# USB_Data_isolation.net
KiCad netlist of a schematic drawn in Altium Designer
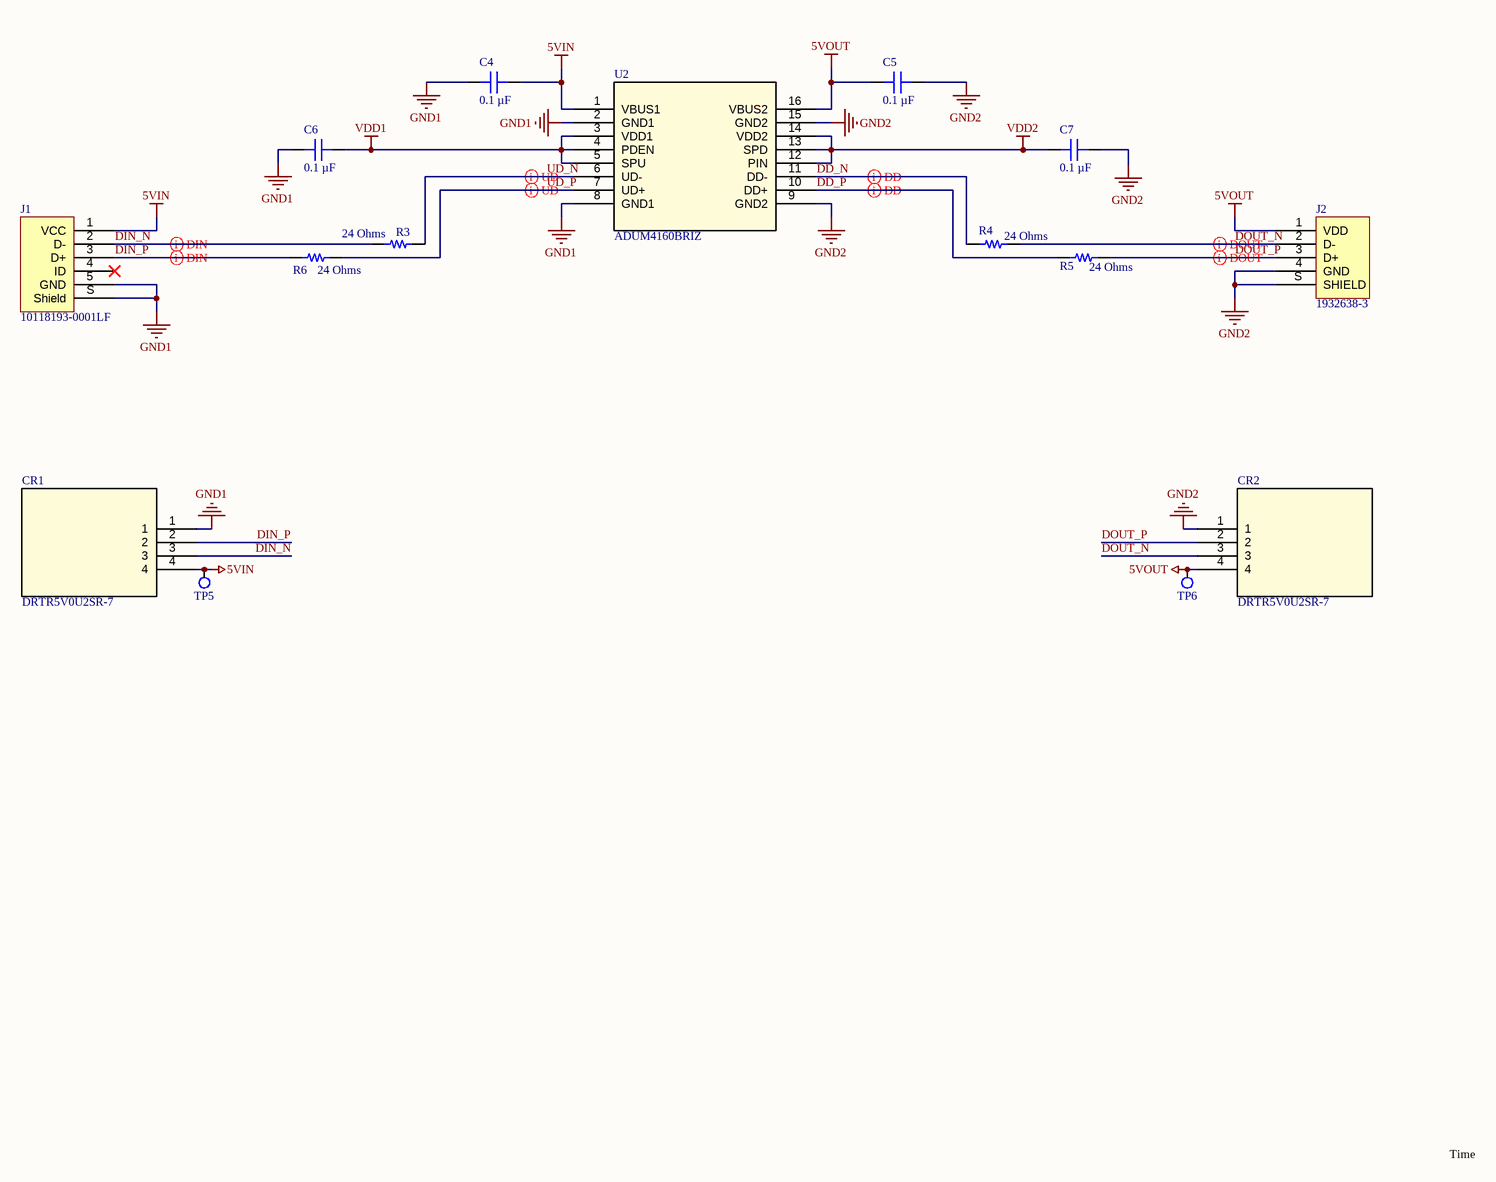
[diagram p0: USB Data isolation.SchDoc]

(export (version "E")
  (design (tool "Eeschema 10.0.6"))
  (components
    (comp (ref "C4")
      (value "0.1 µF")
      (footprint "CAP 0603_1608")
      (description "CAP CER 0.1UF 50V X7R 0603")
      (fields
        (field (name "PART NUMBER") "CL10B104KB8NNNL")
        (field (name "MANUFACTURER") "Samsung Electro-Mechanics")
      )
      (libsource (lib "Celestial Altium Library - altium_library") (part "Capacitor"))
    )
    (comp (ref "C5")
      (value "0.1 µF")
      (footprint "CAP 0603_1608")
      (description "CAP CER 0.1UF 50V X7R 0603")
      (fields
        (field (name "PART NUMBER") "CL10B104KB8NNNL")
        (field (name "MANUFACTURER") "Samsung Electro-Mechanics")
      )
      (libsource (lib "Celestial Altium Library - altium_library") (part "Capacitor"))
    )
    (comp (ref "C6")
      (value "0.1 µF")
      (footprint "CAP 0603_1608")
      (description "CAP CER 0.1UF 50V X7R 0603")
      (fields
        (field (name "PART NUMBER") "CL10B104KB8NNNL")
        (field (name "MANUFACTURER") "Samsung Electro-Mechanics")
      )
      (libsource (lib "Celestial Altium Library - altium_library") (part "Capacitor"))
    )
    (comp (ref "C7")
      (value "0.1 µF")
      (footprint "CAP 0603_1608")
      (description "CAP CER 0.1UF 50V X7R 0603")
      (fields
        (field (name "PART NUMBER") "CL10B104KB8NNNL")
        (field (name "MANUFACTURER") "Samsung Electro-Mechanics")
      )
      (libsource (lib "Celestial Altium Library - altium_library") (part "Capacitor"))
    )
    (comp (ref "CR1")
      (value "DRTR5V0U2SR-7")
      (footprint "SOT143_DIO")
      (description "Dual Channel 5.5 V 0.4 W 1 pF Uni-Dirirectional TVS Diode Array - SOT-143")
      (fields
        (field (name "MANUFACTURER") "Diodes")
        (field (name "COPYRIGHT") "Copyright (C) 2022 Ultra Librarian. All rights reserved.")
      )
      (libsource (lib "") (part "DRTR5V0U2SR-7_1"))
    )
    (comp (ref "CR2")
      (value "DRTR5V0U2SR-7")
      (footprint "SOT143_DIO")
      (description "Dual Channel 5.5 V 0.4 W 1 pF Uni-Dirirectional TVS Diode Array - SOT-143")
      (fields
        (field (name "MANUFACTURER") "Diodes")
        (field (name "COPYRIGHT") "Copyright (C) 2022 Ultra Librarian. All rights reserved.")
      )
      (libsource (lib "USB_isolator") (part "DRTR5V0U2SR-7"))
    )
    (comp (ref "J1")
      (value "10118193-0001LF")
      (footprint "FCI USB 10118193-0001LF")
      (description "CONN RCPT USB2.0 MICRO B SMD R/A")
      (fields (field (name "MANUFACTURER") "Amphenol ICC (FCI)"))
      (libsource (lib "Celestial Altium Library - altium_library") (part "USB 2.0 Type B Micro"))
    )
    (comp (ref "J2")
      (value "1932638-3")
      (footprint "TE 1932638-3 USB2.0A")
      (description "CONN RCPT USB2.0 TYPEA 4P SMD RA")
      (fields (field (name "MANUFACTURER") "TE Connectivity AMP Connectors"))
      (libsource (lib "Celestial Altium Library - altium_library") (part "TE 1932638-3"))
    )
    (comp (ref "R3")
      (value "24 Ohms")
      (footprint "RES 0603_1608")
      (description "RES SMD 24 OHM 0.1% 1/16W 0603")
      (fields
        (field (name "PART NUMBER") "CPF0603B24RE1")
        (field (name "MANUFACTURER") "TE Connectivity Passive Product")
      )
      (libsource (lib "Celestial Altium Library - altium_library") (part "Resistor"))
    )
    (comp (ref "R4")
      (value "24 Ohms")
      (footprint "RES 0603_1608")
      (description "RES SMD 24 OHM 0.1% 1/16W 0603")
      (fields
        (field (name "PART NUMBER") "CPF0603B24RE1")
        (field (name "MANUFACTURER") "TE Connectivity Passive Product")
      )
      (libsource (lib "Celestial Altium Library - altium_library") (part "Resistor"))
    )
    (comp (ref "R5")
      (value "24 Ohms")
      (footprint "RES 0603_1608")
      (description "RES SMD 24 OHM 0.1% 1/16W 0603")
      (fields
        (field (name "PART NUMBER") "CPF0603B24RE1")
        (field (name "MANUFACTURER") "TE Connectivity Passive Product")
      )
      (libsource (lib "Celestial Altium Library - altium_library") (part "Resistor"))
    )
    (comp (ref "R6")
      (value "24 Ohms")
      (footprint "RES 0603_1608")
      (description "RES SMD 24 OHM 0.1% 1/16W 0603")
      (fields
        (field (name "PART NUMBER") "CPF0603B24RE1")
        (field (name "MANUFACTURER") "TE Connectivity Passive Product")
      )
      (libsource (lib "Celestial Altium Library - altium_library") (part "Resistor"))
    )
    (comp (ref "TP5")
      (value "Testpoint_1")
      (footprint "Testpoint_1")
      (description "Testpoint")
      (libsource (lib "USB_isolator") (part "Testpoint_1"))
    )
    (comp (ref "TP6")
      (value "Testpoint_1")
      (footprint "Testpoint_1")
      (description "Testpoint")
      (libsource (lib "USB_isolator") (part "Testpoint_1"))
    )
    (comp (ref "U2")
      (value "ADUM4160BRIZ")
      (footprint "RI_16_1_ADI")
      (description "USB Digital Isolator 5000Vrms 1 Channel 12Mbps 25kV/µs CMTI 16-SOIC (0.295\", 7.50mm Width)")
      (fields (field (name "COPYRIGHT") "Copyright (C) 2022 Ultra Librarian. All rights reserved."))
      (libsource (lib "USB_isolator") (part "ADUM4160BRIZ"))
    )
  )
  (nets
    (net (code "1") (name "/DD_N") (class "Default")
      (node (ref "R4") (pin "1") (pinfunction "1_1") (pintype "passive"))
      (node (ref "U2") (pin "11") (pinfunction "DD-_11") (pintype "passive"))
    )
    (net (code "2") (name "/DD_P") (class "Default")
      (node (ref "R5") (pin "1") (pinfunction "1_1") (pintype "passive"))
      (node (ref "U2") (pin "10") (pinfunction "DD+_10") (pintype "passive"))
    )
    (net (code "3") (name "/DIN_N") (class "Default")
      (node (ref "CR1") (pin "3") (pinfunction "3_3") (pintype "passive"))
      (node (ref "J1") (pin "2") (pinfunction "D-_2") (pintype "passive"))
      (node (ref "R3") (pin "1") (pinfunction "1_1") (pintype "passive"))
    )
    (net (code "4") (name "/DIN_P") (class "Default")
      (node (ref "CR1") (pin "2") (pinfunction "2_2") (pintype "passive"))
      (node (ref "J1") (pin "3") (pinfunction "D+_3") (pintype "passive"))
      (node (ref "R6") (pin "1") (pinfunction "1_1") (pintype "passive"))
    )
    (net (code "5") (name "/DOUT_N") (class "Default")
      (node (ref "CR2") (pin "3") (pinfunction "3_3") (pintype "passive"))
      (node (ref "J2") (pin "2") (pinfunction "D-_2") (pintype "passive"))
      (node (ref "R4") (pin "2") (pinfunction "2_2") (pintype "passive"))
    )
    (net (code "6") (name "/DOUT_P") (class "Default")
      (node (ref "CR2") (pin "2") (pinfunction "2_2") (pintype "passive"))
      (node (ref "J2") (pin "3") (pinfunction "D+_3") (pintype "passive"))
      (node (ref "R5") (pin "2") (pinfunction "2_2") (pintype "passive"))
    )
    (net (code "7") (name "/UD_N") (class "Default")
      (node (ref "R3") (pin "2") (pinfunction "2_2") (pintype "passive"))
      (node (ref "U2") (pin "6") (pinfunction "UD-_6") (pintype "passive"))
    )
    (net (code "8") (name "/UD_P") (class "Default")
      (node (ref "R6") (pin "2") (pinfunction "2_2") (pintype "passive"))
      (node (ref "U2") (pin "7") (pinfunction "UD+_7") (pintype "passive"))
    )
    (net (code "9") (name "5VIN") (class "Default")
      (node (ref "C4") (pin "1") (pinfunction "1_1") (pintype "passive"))
      (node (ref "CR1") (pin "4") (pinfunction "4_4") (pintype "passive"))
      (node (ref "J1") (pin "1") (pinfunction "VCC_1") (pintype "passive"))
      (node (ref "TP5") (pin "1") (pinfunction "1_1") (pintype "passive"))
      (node (ref "U2") (pin "1") (pinfunction "VBUS1_1") (pintype "passive"))
    )
    (net (code "10") (name "5VOUT") (class "Default")
      (node (ref "C5") (pin "2") (pinfunction "2_2") (pintype "passive"))
      (node (ref "CR2") (pin "4") (pinfunction "4_4") (pintype "passive"))
      (node (ref "J2") (pin "1") (pinfunction "VDD_1") (pintype "passive"))
      (node (ref "TP6") (pin "1") (pinfunction "1_1") (pintype "passive"))
      (node (ref "U2") (pin "16") (pinfunction "VBUS2_16") (pintype "passive"))
    )
    (net (code "11") (name "GND1") (class "Default")
      (node (ref "C4") (pin "2") (pinfunction "2_2") (pintype "passive"))
      (node (ref "C6") (pin "2") (pinfunction "2_2") (pintype "passive"))
      (node (ref "CR1") (pin "1") (pinfunction "1_1") (pintype "passive"))
      (node (ref "J1") (pin "5") (pinfunction "GND_5") (pintype "passive"))
      (node (ref "J1") (pin "S") (pinfunction "Shield_S") (pintype "passive"))
      (node (ref "U2") (pin "2") (pinfunction "GND1_2") (pintype "passive"))
      (node (ref "U2") (pin "8") (pinfunction "GND1_8") (pintype "passive"))
    )
    (net (code "12") (name "GND2") (class "Default")
      (node (ref "C5") (pin "1") (pinfunction "1_1") (pintype "passive"))
      (node (ref "C7") (pin "1") (pinfunction "1_1") (pintype "passive"))
      (node (ref "CR2") (pin "1") (pinfunction "1_1") (pintype "passive"))
      (node (ref "J2") (pin "4") (pinfunction "GND_4") (pintype "passive"))
      (node (ref "J2") (pin "S") (pinfunction "SHIELD_S") (pintype "passive"))
      (node (ref "U2") (pin "15") (pinfunction "GND2_15") (pintype "passive"))
      (node (ref "U2") (pin "9") (pinfunction "GND2_9") (pintype "passive"))
    )
    (net (code "13") (name "VDD1") (class "Default")
      (node (ref "C6") (pin "1") (pinfunction "1_1") (pintype "passive"))
      (node (ref "U2") (pin "3") (pinfunction "VDD1_3") (pintype "passive"))
      (node (ref "U2") (pin "4") (pinfunction "PDEN_4") (pintype "passive"))
      (node (ref "U2") (pin "5") (pinfunction "SPU_5") (pintype "passive"))
    )
    (net (code "14") (name "VDD2") (class "Default")
      (node (ref "C7") (pin "2") (pinfunction "2_2") (pintype "passive"))
      (node (ref "U2") (pin "12") (pinfunction "PIN_12") (pintype "passive"))
      (node (ref "U2") (pin "13") (pinfunction "SPD_13") (pintype "passive"))
      (node (ref "U2") (pin "14") (pinfunction "VDD2_14") (pintype "passive"))
    )
    (net (code "15") (name "unconnected-(J1-ID-Pad4)") (class "Default")
      (node (ref "J1") (pin "4") (pinfunction "ID_4") (pintype "passive+no_connect"))
    )
  )
)
